# avr.net
KiCad netlist of a schematic drawn in EAGLE
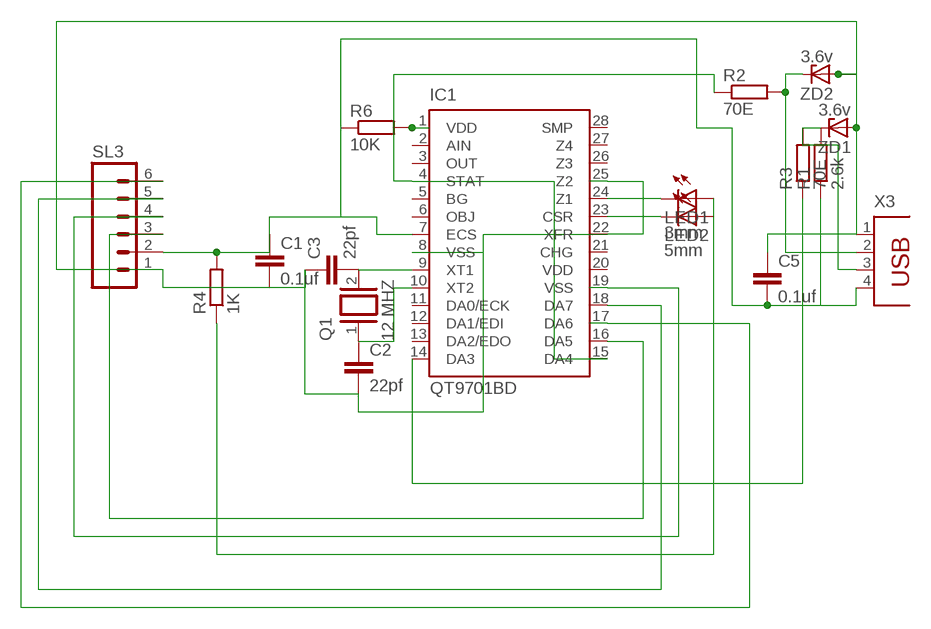
[diagram p0: schematic, sheet 1]

(export (version "E")
  (design (tool "Eeschema 10.0.6"))
  (components
    (comp (ref "C1")
      (value "0.1uf")
      (footprint "eagle-import:C2.5-3")
      (libsource (lib "eagle-import") (part "C2,5-3"))
    )
    (comp (ref "C2")
      (value "22pf")
      (footprint "eagle-import:C2.5-3")
      (libsource (lib "eagle-import") (part "C2,5-3"))
    )
    (comp (ref "C3")
      (value "22pf")
      (footprint "eagle-import:C2.5-3")
      (libsource (lib "eagle-import") (part "C2,5-3"))
    )
    (comp (ref "C5")
      (value "0.1uf")
      (footprint "eagle-import:C2.5-3")
      (libsource (lib "eagle-import") (part "C2,5-3"))
    )
    (comp (ref "IC1")
      (value "QT9701BD")
      (footprint "eagle-import:DIL28-3")
      (libsource (lib "eagle-import") (part "QT9701BD"))
    )
    (comp (ref "LED1")
      (value "3mm")
      (footprint "eagle-import:LED3MM")
      (libsource (lib "eagle-import") (part "LED3MM"))
    )
    (comp (ref "LED2")
      (value "5mm")
      (footprint "eagle-import:LED3MM")
      (libsource (lib "eagle-import") (part "LED3MM"))
    )
    (comp (ref "Q1")
      (value "12 MHZ")
      (footprint "eagle-import:QS")
      (libsource (lib "eagle-import") (part "XTAL/S"))
    )
    (comp (ref "R1")
      (value "2.6k")
      (footprint "eagle-import:0204_7")
      (libsource (lib "eagle-import") (part "R-EU_0204/7"))
    )
    (comp (ref "R2")
      (value "70E")
      (footprint "eagle-import:0204_7")
      (libsource (lib "eagle-import") (part "R-EU_0204/7"))
    )
    (comp (ref "R3")
      (value "70E")
      (footprint "eagle-import:0204_7")
      (libsource (lib "eagle-import") (part "R-EU_0204/7"))
    )
    (comp (ref "R4")
      (value "1K")
      (footprint "eagle-import:0204_7")
      (libsource (lib "eagle-import") (part "R-EU_0204/7"))
    )
    (comp (ref "R6")
      (value "10K")
      (footprint "eagle-import:0204_7")
      (libsource (lib "eagle-import") (part "R-EU_0204/7"))
    )
    (comp (ref "SL3")
      (value "M06")
      (footprint "eagle-import:06P")
      (libsource (lib "eagle-import") (part "M06"))
    )
    (comp (ref "X3")
      (value "PN87520")
      (footprint "eagle-import:PN87520")
      (libsource (lib "eagle-import") (part "PN87520"))
    )
    (comp (ref "ZD1")
      (value "3.6v")
      (footprint "eagle-import:SOD81")
      (libsource (lib "eagle-import") (part "BZD23"))
    )
    (comp (ref "ZD2")
      (value "3.6v")
      (footprint "eagle-import:SOD81")
      (libsource (lib "eagle-import") (part "BZD23"))
    )
  )
  (nets
    (net (code "1") (name "Net-(IC1-CSR)") (class "Default")
      (node (ref "IC1") (pin "23") (pinfunction "CSR_23") (pintype "output"))
      (node (ref "LED2") (pin "K") (pinfunction "C_K") (pintype "passive"))
    )
    (net (code "2") (name "Net-(IC1-DA3)") (class "Default")
      (node (ref "IC1") (pin "14") (pinfunction "DA3_14") (pintype "output"))
      (node (ref "R3") (pin "1") (pinfunction "1_1") (pintype "passive"))
    )
    (net (code "3") (name "Net-(IC1-DA4)") (class "Default")
      (node (ref "IC1") (pin "15") (pinfunction "DA4_15") (pintype "output"))
      (node (ref "IC1") (pin "4") (pinfunction "STAT_4") (pintype "output"))
      (node (ref "R2") (pin "1") (pinfunction "1_1") (pintype "passive"))
    )
    (net (code "4") (name "Net-(IC1-DA5)") (class "Default")
      (node (ref "IC1") (pin "16") (pinfunction "DA5_16") (pintype "output"))
      (node (ref "SL3") (pin "3") (pinfunction "3_3") (pintype "passive"))
    )
    (net (code "5") (name "Net-(IC1-DA6)") (class "Default")
      (node (ref "IC1") (pin "17") (pinfunction "DA6_17") (pintype "output"))
      (node (ref "SL3") (pin "6") (pinfunction "6_6") (pintype "passive"))
    )
    (net (code "6") (name "Net-(IC1-DA7)") (class "Default")
      (node (ref "IC1") (pin "18") (pinfunction "DA7_18") (pintype "output"))
      (node (ref "SL3") (pin "5") (pinfunction "5_5") (pintype "passive"))
    )
    (net (code "7") (name "Net-(IC1-ECS)") (class "Default")
      (node (ref "C1") (pin "1") (pinfunction "1_1") (pintype "passive"))
      (node (ref "C5") (pin "2") (pinfunction "2_2") (pintype "passive"))
      (node (ref "IC1") (pin "7") (pinfunction "ECS_7") (pintype "output"))
      (node (ref "R1") (pin "1") (pinfunction "1_1") (pintype "passive"))
      (node (ref "R4") (pin "2") (pinfunction "2_2") (pintype "passive"))
      (node (ref "R6") (pin "1") (pinfunction "1_1") (pintype "passive"))
      (node (ref "SL3") (pin "2") (pinfunction "2_2") (pintype "passive"))
      (node (ref "X3") (pin "4") (pinfunction "4_4") (pintype "passive"))
    )
    (net (code "8") (name "Net-(IC1-VDD-Pad1)") (class "Default")
      (node (ref "IC1") (pin "1") (pinfunction "VDD_1") (pintype "input"))
      (node (ref "R6") (pin "2") (pinfunction "2_2") (pintype "passive"))
    )
    (net (code "9") (name "Net-(IC1-VSS-Pad19)") (class "Default")
      (node (ref "IC1") (pin "19") (pinfunction "VSS_19") (pintype "input"))
      (node (ref "SL3") (pin "4") (pinfunction "4_4") (pintype "passive"))
    )
    (net (code "10") (name "Net-(IC1-XFR)") (class "Default")
      (node (ref "C1") (pin "2") (pinfunction "2_2") (pintype "passive"))
      (node (ref "C2") (pin "2") (pinfunction "2_2") (pintype "passive"))
      (node (ref "C3") (pin "1") (pinfunction "1_1") (pintype "passive"))
      (node (ref "C5") (pin "1") (pinfunction "1_1") (pintype "passive"))
      (node (ref "IC1") (pin "22") (pinfunction "XFR_22") (pintype "output"))
      (node (ref "IC1") (pin "25") (pinfunction "Z2_25") (pintype "output"))
      (node (ref "IC1") (pin "8") (pinfunction "VSS_8") (pintype "input"))
      (node (ref "SL3") (pin "1") (pinfunction "1_1") (pintype "passive"))
      (node (ref "X3") (pin "1") (pinfunction "1_1") (pintype "passive"))
      (node (ref "ZD1") (pin "A") (pinfunction "A_A") (pintype "passive"))
      (node (ref "ZD2") (pin "A") (pinfunction "A_A") (pintype "passive"))
    )
    (net (code "11") (name "Net-(IC1-XT1)") (class "Default")
      (node (ref "C3") (pin "2") (pinfunction "2_2") (pintype "passive"))
      (node (ref "IC1") (pin "9") (pinfunction "XT1_9") (pintype "input"))
      (node (ref "Q1") (pin "2") (pinfunction "2_2") (pintype "passive"))
    )
    (net (code "12") (name "Net-(IC1-XT2)") (class "Default")
      (node (ref "C2") (pin "1") (pinfunction "1_1") (pintype "passive"))
      (node (ref "IC1") (pin "10") (pinfunction "XT2_10") (pintype "output"))
      (node (ref "Q1") (pin "1") (pinfunction "1_1") (pintype "passive"))
    )
    (net (code "13") (name "Net-(IC1-Z1)") (class "Default")
      (node (ref "IC1") (pin "24") (pinfunction "Z1_24") (pintype "output"))
      (node (ref "LED1") (pin "K") (pinfunction "C_K") (pintype "passive"))
    )
    (net (code "14") (name "Net-(LED1-PadA)") (class "Default")
      (node (ref "LED1") (pin "A") (pinfunction "A_A") (pintype "passive"))
      (node (ref "LED2") (pin "A") (pinfunction "A_A") (pintype "passive"))
      (node (ref "R4") (pin "1") (pinfunction "1_1") (pintype "passive"))
    )
    (net (code "15") (name "Net-(R1-Pad2)") (class "Default")
      (node (ref "R1") (pin "2") (pinfunction "2_2") (pintype "passive"))
      (node (ref "R3") (pin "2") (pinfunction "2_2") (pintype "passive"))
      (node (ref "X3") (pin "3") (pinfunction "3_3") (pintype "passive"))
      (node (ref "ZD1") (pin "C") (pinfunction "C_C") (pintype "passive"))
    )
    (net (code "16") (name "Net-(R2-Pad2)") (class "Default")
      (node (ref "R2") (pin "2") (pinfunction "2_2") (pintype "passive"))
      (node (ref "X3") (pin "2") (pinfunction "2_2") (pintype "passive"))
      (node (ref "ZD2") (pin "C") (pinfunction "C_C") (pintype "passive"))
    )
    (net (code "17") (name "unconnected-(IC1-AIN-Pad2)") (class "Default")
      (node (ref "IC1") (pin "2") (pinfunction "AIN_2") (pintype "input"))
    )
    (net (code "18") (name "unconnected-(IC1-BG-Pad5)") (class "Default")
      (node (ref "IC1") (pin "5") (pinfunction "BG_5") (pintype "input"))
    )
    (net (code "19") (name "unconnected-(IC1-CHG-Pad21)") (class "Default")
      (node (ref "IC1") (pin "21") (pinfunction "CHG_21") (pintype "output"))
    )
    (net (code "20") (name "unconnected-(IC1-DA0{slash}ECK-Pad11)") (class "Default")
      (node (ref "IC1") (pin "11") (pinfunction "DA0/ECK_11") (pintype "output"))
    )
    (net (code "21") (name "unconnected-(IC1-DA1{slash}EDI-Pad12)") (class "Default")
      (node (ref "IC1") (pin "12") (pinfunction "DA1/EDI_12") (pintype "output"))
    )
    (net (code "22") (name "unconnected-(IC1-DA2{slash}EDO-Pad13)") (class "Default")
      (node (ref "IC1") (pin "13") (pinfunction "DA2/EDO_13") (pintype "output"))
    )
    (net (code "23") (name "unconnected-(IC1-OBJ-Pad6)") (class "Default")
      (node (ref "IC1") (pin "6") (pinfunction "OBJ_6") (pintype "input"))
    )
    (net (code "24") (name "unconnected-(IC1-OUT-Pad3)") (class "Default")
      (node (ref "IC1") (pin "3") (pinfunction "OUT_3") (pintype "output"))
    )
    (net (code "25") (name "unconnected-(IC1-SMP-Pad28)") (class "Default")
      (node (ref "IC1") (pin "28") (pinfunction "SMP_28") (pintype "output"))
    )
    (net (code "26") (name "unconnected-(IC1-VDD-Pad20)") (class "Default")
      (node (ref "IC1") (pin "20") (pinfunction "VDD_20") (pintype "input"))
    )
    (net (code "27") (name "unconnected-(IC1-Z3-Pad26)") (class "Default")
      (node (ref "IC1") (pin "26") (pinfunction "Z3_26") (pintype "output"))
    )
    (net (code "28") (name "unconnected-(IC1-Z4-Pad27)") (class "Default")
      (node (ref "IC1") (pin "27") (pinfunction "Z4_27") (pintype "output"))
    )
  )
)
